# Spresense_PLC__Rev1-02.net
KiCad netlist of a schematic drawn in EAGLE
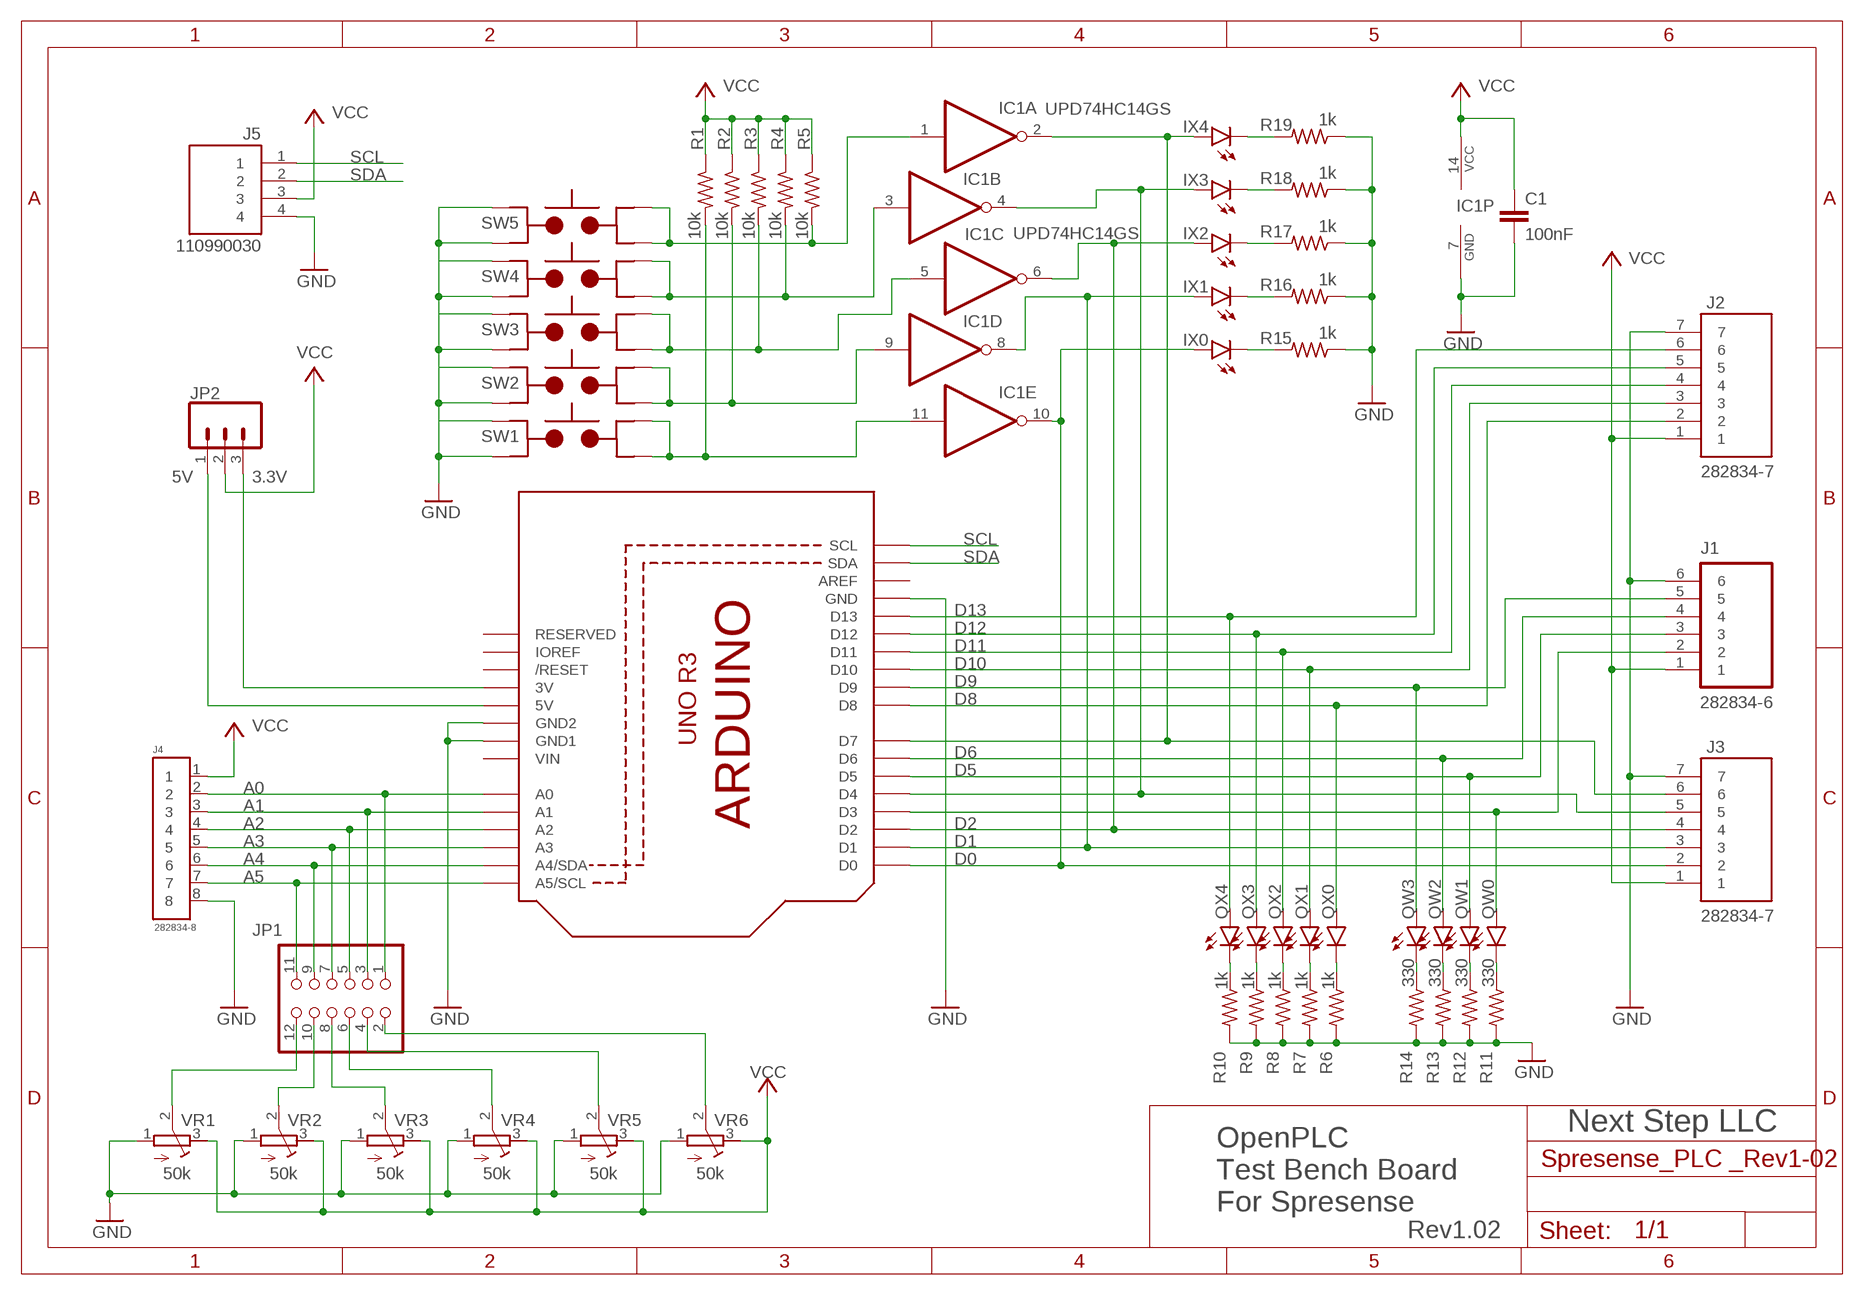
[diagram p0: schematic, sheet 1]

(export (version "E")
  (design (tool "Eeschema 10.0.6"))
  (components
    (comp (ref "C1")
      (value "100nF")
      (footprint "eagle-import:C0603")
      (libsource (lib "eagle-import") (part "C-EUC0603"))
    )
    (comp (ref "IC1")
      (value "UPD74HC14GS")
      (footprint "eagle-import:SO14")
      (libsource (lib "eagle-import") (part "7404DALS"))
    )
    (comp (ref "IX0")
      (value "LEDCHIP-LED0603")
      (footprint "eagle-import:CHIP-LED0603")
      (libsource (lib "eagle-import") (part "LEDCHIP-LED0603"))
    )
    (comp (ref "IX1")
      (value "LEDCHIP-LED0603")
      (footprint "eagle-import:CHIP-LED0603")
      (libsource (lib "eagle-import") (part "LEDCHIP-LED0603"))
    )
    (comp (ref "IX2")
      (value "LEDCHIP-LED0603")
      (footprint "eagle-import:CHIP-LED0603")
      (libsource (lib "eagle-import") (part "LEDCHIP-LED0603"))
    )
    (comp (ref "IX3")
      (value "LEDCHIP-LED0603")
      (footprint "eagle-import:CHIP-LED0603")
      (libsource (lib "eagle-import") (part "LEDCHIP-LED0603"))
    )
    (comp (ref "IX4")
      (value "LEDCHIP-LED0603")
      (footprint "eagle-import:CHIP-LED0603")
      (libsource (lib "eagle-import") (part "LEDCHIP-LED0603"))
    )
    (comp (ref "J1")
      (value "282834-6")
      (footprint "eagle-import:TE_282834-6")
      (fields (field (name "MF") "TE Connectivity"))
      (libsource (lib "eagle-import") (part "282834-6"))
    )
    (comp (ref "J2")
      (value "282834-7")
      (footprint "eagle-import:TE_282834-7")
      (fields (field (name "MF") "TE Connectivity"))
      (libsource (lib "eagle-import") (part "282834-7"))
    )
    (comp (ref "J3")
      (value "282834-7")
      (footprint "eagle-import:TE_282834-7")
      (fields (field (name "MF") "TE Connectivity"))
      (libsource (lib "eagle-import") (part "282834-7"))
    )
    (comp (ref "J4")
      (value "282834-8")
      (footprint "eagle-import:HDRV8W85P254_8X1_2078X650X1000")
      (fields (field (name "MF") "TE Connectivity"))
      (libsource (lib "eagle-import") (part "282834-8"))
    )
    (comp (ref "J5")
      (value "110990030")
      (footprint "eagle-import:SEEED_110990030")
      (fields (field (name "MF") "Seeed Technology Co., Ltd"))
      (libsource (lib "eagle-import") (part "110990030"))
    )
    (comp (ref "JP1")
      (value "PINHD-2X6")
      (footprint "eagle-import:2X06")
      (libsource (lib "eagle-import") (part "PINHD-2X6"))
    )
    (comp (ref "JP2")
      (value "455-1750-1-ND")
      (footprint "eagle-import:1X03")
      (libsource (lib "eagle-import") (part "CONN_03"))
    )
    (comp (ref "QW0")
      (value "LEDCHIP-LED0603")
      (footprint "eagle-import:CHIP-LED0603")
      (libsource (lib "eagle-import") (part "LEDCHIP-LED0603"))
    )
    (comp (ref "QW1")
      (value "LEDCHIP-LED0603")
      (footprint "eagle-import:CHIP-LED0603")
      (libsource (lib "eagle-import") (part "LEDCHIP-LED0603"))
    )
    (comp (ref "QW2")
      (value "LEDCHIP-LED0603")
      (footprint "eagle-import:CHIP-LED0603")
      (libsource (lib "eagle-import") (part "LEDCHIP-LED0603"))
    )
    (comp (ref "QW3")
      (value "LEDCHIP-LED0603")
      (footprint "eagle-import:CHIP-LED0603")
      (libsource (lib "eagle-import") (part "LEDCHIP-LED0603"))
    )
    (comp (ref "QX0")
      (value "LEDCHIP-LED0603")
      (footprint "eagle-import:CHIP-LED0603")
      (libsource (lib "eagle-import") (part "LEDCHIP-LED0603"))
    )
    (comp (ref "QX1")
      (value "LEDCHIP-LED0603")
      (footprint "eagle-import:CHIP-LED0603")
      (libsource (lib "eagle-import") (part "LEDCHIP-LED0603"))
    )
    (comp (ref "QX2")
      (value "LEDCHIP-LED0603")
      (footprint "eagle-import:CHIP-LED0603")
      (libsource (lib "eagle-import") (part "LEDCHIP-LED0603"))
    )
    (comp (ref "QX3")
      (value "LEDCHIP-LED0603")
      (footprint "eagle-import:CHIP-LED0603")
      (libsource (lib "eagle-import") (part "LEDCHIP-LED0603"))
    )
    (comp (ref "QX4")
      (value "LEDCHIP-LED0603")
      (footprint "eagle-import:CHIP-LED0603")
      (libsource (lib "eagle-import") (part "LEDCHIP-LED0603"))
    )
    (comp (ref "R1")
      (value "10k")
      (footprint "eagle-import:R0603")
      (libsource (lib "eagle-import") (part "R-US_R0603"))
    )
    (comp (ref "R2")
      (value "10k")
      (footprint "eagle-import:R0603")
      (libsource (lib "eagle-import") (part "R-US_R0603"))
    )
    (comp (ref "R3")
      (value "10k")
      (footprint "eagle-import:R0603")
      (libsource (lib "eagle-import") (part "R-US_R0603"))
    )
    (comp (ref "R4")
      (value "10k")
      (footprint "eagle-import:R0603")
      (libsource (lib "eagle-import") (part "R-US_R0603"))
    )
    (comp (ref "R5")
      (value "10k")
      (footprint "eagle-import:R0603")
      (libsource (lib "eagle-import") (part "R-US_R0603"))
    )
    (comp (ref "R6")
      (value "1k")
      (footprint "eagle-import:R0603")
      (libsource (lib "eagle-import") (part "R-US_R0603"))
    )
    (comp (ref "R7")
      (value "1k")
      (footprint "eagle-import:R0603")
      (libsource (lib "eagle-import") (part "R-US_R0603"))
    )
    (comp (ref "R8")
      (value "1k")
      (footprint "eagle-import:R0603")
      (libsource (lib "eagle-import") (part "R-US_R0603"))
    )
    (comp (ref "R9")
      (value "1k")
      (footprint "eagle-import:R0603")
      (libsource (lib "eagle-import") (part "R-US_R0603"))
    )
    (comp (ref "R10")
      (value "1k")
      (footprint "eagle-import:R0603")
      (libsource (lib "eagle-import") (part "R-US_R0603"))
    )
    (comp (ref "R11")
      (value "330")
      (footprint "eagle-import:R0603")
      (libsource (lib "eagle-import") (part "R-US_R0603"))
    )
    (comp (ref "R12")
      (value "330")
      (footprint "eagle-import:R0603")
      (libsource (lib "eagle-import") (part "R-US_R0603"))
    )
    (comp (ref "R13")
      (value "330")
      (footprint "eagle-import:R0603")
      (libsource (lib "eagle-import") (part "R-US_R0603"))
    )
    (comp (ref "R14")
      (value "330")
      (footprint "eagle-import:R0603")
      (libsource (lib "eagle-import") (part "R-US_R0603"))
    )
    (comp (ref "R15")
      (value "1k")
      (footprint "eagle-import:R0603")
      (libsource (lib "eagle-import") (part "R-US_R0603"))
    )
    (comp (ref "R16")
      (value "1k")
      (footprint "eagle-import:R0603")
      (libsource (lib "eagle-import") (part "R-US_R0603"))
    )
    (comp (ref "R17")
      (value "1k")
      (footprint "eagle-import:R0603")
      (libsource (lib "eagle-import") (part "R-US_R0603"))
    )
    (comp (ref "R18")
      (value "1k")
      (footprint "eagle-import:R0603")
      (libsource (lib "eagle-import") (part "R-US_R0603"))
    )
    (comp (ref "R19")
      (value "1k")
      (footprint "eagle-import:R0603")
      (libsource (lib "eagle-import") (part "R-US_R0603"))
    )
    (comp (ref "SW1")
      (value "TL3342F160QG/TR")
      (footprint "eagle-import:SW_TL3342F160QG_TR")
      (fields (field (name "MF") "E-Switch"))
      (libsource (lib "eagle-import") (part "TL3342F160QG/TR"))
    )
    (comp (ref "SW2")
      (value "TL3342F160QG/TR")
      (footprint "eagle-import:SW_TL3342F160QG_TR")
      (fields (field (name "MF") "E-Switch"))
      (libsource (lib "eagle-import") (part "TL3342F160QG/TR"))
    )
    (comp (ref "SW3")
      (value "TL3342F160QG/TR")
      (footprint "eagle-import:SW_TL3342F160QG_TR")
      (fields (field (name "MF") "E-Switch"))
      (libsource (lib "eagle-import") (part "TL3342F160QG/TR"))
    )
    (comp (ref "SW4")
      (value "TL3342F160QG/TR")
      (footprint "eagle-import:SW_TL3342F160QG_TR")
      (fields (field (name "MF") "E-Switch"))
      (libsource (lib "eagle-import") (part "TL3342F160QG/TR"))
    )
    (comp (ref "SW5")
      (value "TL3342F160QG/TR")
      (footprint "eagle-import:SW_TL3342F160QG_TR")
      (fields (field (name "MF") "E-Switch"))
      (libsource (lib "eagle-import") (part "TL3342F160QG/TR"))
    )
    (comp (ref "U1")
      (value "ARDUINOR3-DIMENSION")
      (footprint "eagle-import:ARDUINOR3")
      (libsource (lib "eagle-import") (part "ARDUINOR3-DIMENSION"))
    )
    (comp (ref "VR1")
      (value "50k")
      (footprint "eagle-import:RTRIM3339P")
      (libsource (lib "eagle-import") (part "R-TRIMM3339P"))
    )
    (comp (ref "VR2")
      (value "50k")
      (footprint "eagle-import:RTRIM3339P")
      (libsource (lib "eagle-import") (part "R-TRIMM3339P"))
    )
    (comp (ref "VR3")
      (value "50k")
      (footprint "eagle-import:RTRIM3339P")
      (libsource (lib "eagle-import") (part "R-TRIMM3339P"))
    )
    (comp (ref "VR4")
      (value "50k")
      (footprint "eagle-import:RTRIM3339P")
      (libsource (lib "eagle-import") (part "R-TRIMM3339P"))
    )
    (comp (ref "VR5")
      (value "50k")
      (footprint "eagle-import:RTRIM3339P")
      (libsource (lib "eagle-import") (part "R-TRIMM3339P"))
    )
    (comp (ref "VR6")
      (value "50k")
      (footprint "eagle-import:RTRIM3339P")
      (libsource (lib "eagle-import") (part "R-TRIMM3339P"))
    )
  )
  (nets
    (net (code "1") (name "/A0") (class "Default")
      (node (ref "J4") (pin "2") (pinfunction "2_2") (pintype "passive"))
      (node (ref "JP1") (pin "1") (pinfunction "1_1") (pintype "passive"))
      (node (ref "U1") (pin "A0") (pinfunction "A0_A0") (pintype "bidirectional"))
    )
    (net (code "2") (name "/A1") (class "Default")
      (node (ref "J4") (pin "3") (pinfunction "3_3") (pintype "passive"))
      (node (ref "JP1") (pin "3") (pinfunction "3_3") (pintype "passive"))
      (node (ref "U1") (pin "A1") (pinfunction "A1_A1") (pintype "bidirectional"))
    )
    (net (code "3") (name "/A2") (class "Default")
      (node (ref "J4") (pin "4") (pinfunction "4_4") (pintype "passive"))
      (node (ref "JP1") (pin "5") (pinfunction "5_5") (pintype "passive"))
      (node (ref "U1") (pin "A2") (pinfunction "A2_A2") (pintype "bidirectional"))
    )
    (net (code "4") (name "/A3") (class "Default")
      (node (ref "J4") (pin "5") (pinfunction "5_5") (pintype "passive"))
      (node (ref "JP1") (pin "7") (pinfunction "7_7") (pintype "passive"))
      (node (ref "U1") (pin "A3") (pinfunction "A3_A3") (pintype "bidirectional"))
    )
    (net (code "5") (name "/A4") (class "Default")
      (node (ref "J4") (pin "6") (pinfunction "6_6") (pintype "passive"))
      (node (ref "JP1") (pin "9") (pinfunction "9_9") (pintype "passive"))
      (node (ref "U1") (pin "A4") (pinfunction "A4/SDA_A4") (pintype "bidirectional"))
    )
    (net (code "6") (name "/A5") (class "Default")
      (node (ref "J4") (pin "7") (pinfunction "7_7") (pintype "passive"))
      (node (ref "JP1") (pin "11") (pinfunction "11_11") (pintype "passive"))
      (node (ref "U1") (pin "A5") (pinfunction "A5/SCL_A5") (pintype "bidirectional"))
    )
    (net (code "7") (name "/D0") (class "Default")
      (node (ref "IC1") (pin "10") (pinfunction "O_10") (pintype "output"))
      (node (ref "IX0") (pin "A") (pinfunction "A_A") (pintype "passive"))
      (node (ref "J3") (pin "2") (pinfunction "2_2") (pintype "passive"))
      (node (ref "U1") (pin "D0") (pinfunction "D0_D0") (pintype "bidirectional"))
    )
    (net (code "8") (name "/D1") (class "Default")
      (node (ref "IC1") (pin "8") (pinfunction "O_8") (pintype "output"))
      (node (ref "IX1") (pin "A") (pinfunction "A_A") (pintype "passive"))
      (node (ref "J3") (pin "3") (pinfunction "3_3") (pintype "passive"))
      (node (ref "U1") (pin "D1") (pinfunction "D1_D1") (pintype "bidirectional"))
    )
    (net (code "9") (name "/D2") (class "Default")
      (node (ref "IC1") (pin "6") (pinfunction "O_6") (pintype "output"))
      (node (ref "IX2") (pin "A") (pinfunction "A_A") (pintype "passive"))
      (node (ref "J3") (pin "4") (pinfunction "4_4") (pintype "passive"))
      (node (ref "U1") (pin "D2") (pinfunction "D2_D2") (pintype "bidirectional"))
    )
    (net (code "10") (name "/D5") (class "Default")
      (node (ref "IC1") (pin "4") (pinfunction "O_4") (pintype "output"))
      (node (ref "IX3") (pin "A") (pinfunction "A_A") (pintype "passive"))
      (node (ref "J3") (pin "5") (pinfunction "5_5") (pintype "passive"))
      (node (ref "U1") (pin "D4") (pinfunction "D4_D4") (pintype "bidirectional"))
    )
    (net (code "11") (name "/D6") (class "Default")
      (node (ref "IC1") (pin "2") (pinfunction "O_2") (pintype "output"))
      (node (ref "IX4") (pin "A") (pinfunction "A_A") (pintype "passive"))
      (node (ref "J3") (pin "6") (pinfunction "6_6") (pintype "passive"))
      (node (ref "U1") (pin "D7") (pinfunction "D7_D7") (pintype "bidirectional"))
    )
    (net (code "12") (name "/D8") (class "Default")
      (node (ref "J2") (pin "2") (pinfunction "2_2") (pintype "passive"))
      (node (ref "QX0") (pin "A") (pinfunction "A_A") (pintype "passive"))
      (node (ref "U1") (pin "D8") (pinfunction "D8_D8") (pintype "bidirectional"))
    )
    (net (code "13") (name "/D9") (class "Default")
      (node (ref "J1") (pin "5") (pinfunction "5_5") (pintype "passive"))
      (node (ref "QW3") (pin "A") (pinfunction "A_A") (pintype "passive"))
      (node (ref "U1") (pin "D9") (pinfunction "D9_D9") (pintype "bidirectional"))
    )
    (net (code "14") (name "/D10") (class "Default")
      (node (ref "J2") (pin "3") (pinfunction "3_3") (pintype "passive"))
      (node (ref "QX1") (pin "A") (pinfunction "A_A") (pintype "passive"))
      (node (ref "U1") (pin "D10") (pinfunction "D10_D10") (pintype "bidirectional"))
    )
    (net (code "15") (name "/D11") (class "Default")
      (node (ref "J2") (pin "4") (pinfunction "4_4") (pintype "passive"))
      (node (ref "QX2") (pin "A") (pinfunction "A_A") (pintype "passive"))
      (node (ref "U1") (pin "D11") (pinfunction "D11_D11") (pintype "bidirectional"))
    )
    (net (code "16") (name "/D12") (class "Default")
      (node (ref "J2") (pin "5") (pinfunction "5_5") (pintype "passive"))
      (node (ref "QX3") (pin "A") (pinfunction "A_A") (pintype "passive"))
      (node (ref "U1") (pin "D12") (pinfunction "D12_D12") (pintype "bidirectional"))
    )
    (net (code "17") (name "/D13") (class "Default")
      (node (ref "J2") (pin "6") (pinfunction "6_6") (pintype "passive"))
      (node (ref "QX4") (pin "A") (pinfunction "A_A") (pintype "passive"))
      (node (ref "U1") (pin "D13") (pinfunction "D13_D13") (pintype "bidirectional"))
    )
    (net (code "18") (name "/SCL") (class "Default")
      (node (ref "J5") (pin "1") (pinfunction "1_1") (pintype "passive"))
      (node (ref "U1") (pin "SCL") (pinfunction "SCL_SCL") (pintype "bidirectional"))
    )
    (net (code "19") (name "/SDA") (class "Default")
      (node (ref "J5") (pin "2") (pinfunction "2_2") (pintype "passive"))
      (node (ref "U1") (pin "SDA") (pinfunction "SDA_SDA") (pintype "bidirectional"))
    )
    (net (code "20") (name "/VIN") (class "Default")
      (node (ref "U1") (pin "VIN") (pinfunction "VIN_VIN") (pintype "power_in"))
    )
    (net (code "21") (name "GND") (class "Default")
      (node (ref "C1") (pin "2") (pinfunction "2_2") (pintype "passive"))
      (node (ref "IC1") (pin "7") (pinfunction "GND_7") (pintype "power_in"))
      (node (ref "J1") (pin "6") (pinfunction "6_6") (pintype "passive"))
      (node (ref "J2") (pin "7") (pinfunction "7_7") (pintype "passive"))
      (node (ref "J3") (pin "7") (pinfunction "7_7") (pintype "passive"))
      (node (ref "J4") (pin "8") (pinfunction "8_8") (pintype "passive"))
      (node (ref "J5") (pin "4") (pinfunction "4_4") (pintype "passive"))
      (node (ref "R10") (pin "2") (pinfunction "2_2") (pintype "passive"))
      (node (ref "R11") (pin "2") (pinfunction "2_2") (pintype "passive"))
      (node (ref "R12") (pin "2") (pinfunction "2_2") (pintype "passive"))
      (node (ref "R13") (pin "2") (pinfunction "2_2") (pintype "passive"))
      (node (ref "R14") (pin "2") (pinfunction "2_2") (pintype "passive"))
      (node (ref "R15") (pin "1") (pinfunction "1_1") (pintype "passive"))
      (node (ref "R16") (pin "1") (pinfunction "1_1") (pintype "passive"))
      (node (ref "R17") (pin "1") (pinfunction "1_1") (pintype "passive"))
      (node (ref "R18") (pin "1") (pinfunction "1_1") (pintype "passive"))
      (node (ref "R19") (pin "1") (pinfunction "1_1") (pintype "passive"))
      (node (ref "R6") (pin "2") (pinfunction "2_2") (pintype "passive"))
      (node (ref "R7") (pin "2") (pinfunction "2_2") (pintype "passive"))
      (node (ref "R8") (pin "2") (pinfunction "2_2") (pintype "passive"))
      (node (ref "R9") (pin "2") (pinfunction "2_2") (pintype "passive"))
      (node (ref "SW1") (pin "3") (pinfunction "3_3") (pintype "passive"))
      (node (ref "SW1") (pin "4") (pinfunction "4_4") (pintype "passive"))
      (node (ref "SW2") (pin "3") (pinfunction "3_3") (pintype "passive"))
      (node (ref "SW2") (pin "4") (pinfunction "4_4") (pintype "passive"))
      (node (ref "SW3") (pin "3") (pinfunction "3_3") (pintype "passive"))
      (node (ref "SW3") (pin "4") (pinfunction "4_4") (pintype "passive"))
      (node (ref "SW4") (pin "3") (pinfunction "3_3") (pintype "passive"))
      (node (ref "SW4") (pin "4") (pinfunction "4_4") (pintype "passive"))
      (node (ref "SW5") (pin "3") (pinfunction "3_3") (pintype "passive"))
      (node (ref "SW5") (pin "4") (pinfunction "4_4") (pintype "passive"))
      (node (ref "U1") (pin "GND") (pinfunction "GND_GND") (pintype "power_in"))
      (node (ref "U1") (pin "GND1") (pinfunction "GND1_GND1") (pintype "power_in"))
      (node (ref "U1") (pin "GND2") (pinfunction "GND2_GND2") (pintype "power_in"))
      (node (ref "VR1") (pin "1") (pinfunction "A_1") (pintype "passive"))
      (node (ref "VR2") (pin "1") (pinfunction "A_1") (pintype "passive"))
      (node (ref "VR3") (pin "1") (pinfunction "A_1") (pintype "passive"))
      (node (ref "VR4") (pin "1") (pinfunction "A_1") (pintype "passive"))
      (node (ref "VR5") (pin "1") (pinfunction "A_1") (pintype "passive"))
      (node (ref "VR6") (pin "1") (pinfunction "A_1") (pintype "passive"))
    )
    (net (code "22") (name "Net-(IC1A-I)") (class "Default")
      (node (ref "IC1") (pin "1") (pinfunction "I_1") (pintype "input"))
      (node (ref "R5") (pin "2") (pinfunction "2_2") (pintype "passive"))
      (node (ref "SW5") (pin "1") (pinfunction "1_1") (pintype "passive"))
      (node (ref "SW5") (pin "2") (pinfunction "2_2") (pintype "passive"))
    )
    (net (code "23") (name "Net-(IC1B-I)") (class "Default")
      (node (ref "IC1") (pin "3") (pinfunction "I_3") (pintype "input"))
      (node (ref "R4") (pin "2") (pinfunction "2_2") (pintype "passive"))
      (node (ref "SW4") (pin "1") (pinfunction "1_1") (pintype "passive"))
      (node (ref "SW4") (pin "2") (pinfunction "2_2") (pintype "passive"))
    )
    (net (code "24") (name "Net-(IC1C-I)") (class "Default")
      (node (ref "IC1") (pin "5") (pinfunction "I_5") (pintype "input"))
      (node (ref "R3") (pin "2") (pinfunction "2_2") (pintype "passive"))
      (node (ref "SW3") (pin "1") (pinfunction "1_1") (pintype "passive"))
      (node (ref "SW3") (pin "2") (pinfunction "2_2") (pintype "passive"))
    )
    (net (code "25") (name "Net-(IC1D-I)") (class "Default")
      (node (ref "IC1") (pin "9") (pinfunction "I_9") (pintype "input"))
      (node (ref "R2") (pin "2") (pinfunction "2_2") (pintype "passive"))
      (node (ref "SW2") (pin "1") (pinfunction "1_1") (pintype "passive"))
      (node (ref "SW2") (pin "2") (pinfunction "2_2") (pintype "passive"))
    )
    (net (code "26") (name "Net-(IC1E-I)") (class "Default")
      (node (ref "IC1") (pin "11") (pinfunction "I_11") (pintype "input"))
      (node (ref "R1") (pin "2") (pinfunction "2_2") (pintype "passive"))
      (node (ref "SW1") (pin "1") (pinfunction "1_1") (pintype "passive"))
      (node (ref "SW1") (pin "2") (pinfunction "2_2") (pintype "passive"))
    )
    (net (code "27") (name "Net-(IX0-PadC)") (class "Default")
      (node (ref "IX0") (pin "C") (pinfunction "C_C") (pintype "passive"))
      (node (ref "R15") (pin "2") (pinfunction "2_2") (pintype "passive"))
    )
    (net (code "28") (name "Net-(IX1-PadC)") (class "Default")
      (node (ref "IX1") (pin "C") (pinfunction "C_C") (pintype "passive"))
      (node (ref "R16") (pin "2") (pinfunction "2_2") (pintype "passive"))
    )
    (net (code "29") (name "Net-(IX2-PadC)") (class "Default")
      (node (ref "IX2") (pin "C") (pinfunction "C_C") (pintype "passive"))
      (node (ref "R17") (pin "2") (pinfunction "2_2") (pintype "passive"))
    )
    (net (code "30") (name "Net-(IX3-PadC)") (class "Default")
      (node (ref "IX3") (pin "C") (pinfunction "C_C") (pintype "passive"))
      (node (ref "R18") (pin "2") (pinfunction "2_2") (pintype "passive"))
    )
    (net (code "31") (name "Net-(IX4-PadC)") (class "Default")
      (node (ref "IX4") (pin "C") (pinfunction "C_C") (pintype "passive"))
      (node (ref "R19") (pin "2") (pinfunction "2_2") (pintype "passive"))
    )
    (net (code "32") (name "Net-(J1-Pad2)") (class "Default")
      (node (ref "J1") (pin "2") (pinfunction "2_2") (pintype "passive"))
      (node (ref "QW0") (pin "A") (pinfunction "A_A") (pintype "passive"))
      (node (ref "U1") (pin "D3") (pinfunction "D3_D3") (pintype "bidirectional"))
    )
    (net (code "33") (name "Net-(J1-Pad3)") (class "Default")
      (node (ref "J1") (pin "3") (pinfunction "3_3") (pintype "passive"))
      (node (ref "QW1") (pin "A") (pinfunction "A_A") (pintype "passive"))
      (node (ref "U1") (pin "D5") (pinfunction "D5_D5") (pintype "bidirectional"))
    )
    (net (code "34") (name "Net-(J1-Pad4)") (class "Default")
      (node (ref "J1") (pin "4") (pinfunction "4_4") (pintype "passive"))
      (node (ref "QW2") (pin "A") (pinfunction "A_A") (pintype "passive"))
      (node (ref "U1") (pin "D6") (pinfunction "D6_D6") (pintype "bidirectional"))
    )
    (net (code "35") (name "Net-(JP2-Pad1)") (class "Default")
      (node (ref "JP2") (pin "1") (pinfunction "1_1") (pintype "passive"))
      (node (ref "U1") (pin "5V") (pinfunction "5V_5V") (pintype "power_in"))
    )
    (net (code "36") (name "Net-(JP2-Pad3)") (class "Default")
      (node (ref "JP2") (pin "3") (pinfunction "3_3") (pintype "passive"))
      (node (ref "U1") (pin "3V") (pinfunction "3V_3V") (pintype "power_in"))
    )
    (net (code "37") (name "Net-(QW0-PadC)") (class "Default")
      (node (ref "QW0") (pin "C") (pinfunction "C_C") (pintype "passive"))
      (node (ref "R11") (pin "1") (pinfunction "1_1") (pintype "passive"))
    )
    (net (code "38") (name "Net-(QW1-PadC)") (class "Default")
      (node (ref "QW1") (pin "C") (pinfunction "C_C") (pintype "passive"))
      (node (ref "R12") (pin "1") (pinfunction "1_1") (pintype "passive"))
    )
    (net (code "39") (name "Net-(QW2-PadC)") (class "Default")
      (node (ref "QW2") (pin "C") (pinfunction "C_C") (pintype "passive"))
      (node (ref "R13") (pin "1") (pinfunction "1_1") (pintype "passive"))
    )
    (net (code "40") (name "Net-(QW3-PadC)") (class "Default")
      (node (ref "QW3") (pin "C") (pinfunction "C_C") (pintype "passive"))
      (node (ref "R14") (pin "1") (pinfunction "1_1") (pintype "passive"))
    )
    (net (code "41") (name "Net-(QX0-PadC)") (class "Default")
      (node (ref "QX0") (pin "C") (pinfunction "C_C") (pintype "passive"))
      (node (ref "R6") (pin "1") (pinfunction "1_1") (pintype "passive"))
    )
    (net (code "42") (name "Net-(QX1-PadC)") (class "Default")
      (node (ref "QX1") (pin "C") (pinfunction "C_C") (pintype "passive"))
      (node (ref "R7") (pin "1") (pinfunction "1_1") (pintype "passive"))
    )
    (net (code "43") (name "Net-(QX2-PadC)") (class "Default")
      (node (ref "QX2") (pin "C") (pinfunction "C_C") (pintype "passive"))
      (node (ref "R8") (pin "1") (pinfunction "1_1") (pintype "passive"))
    )
    (net (code "44") (name "Net-(QX3-PadC)") (class "Default")
      (node (ref "QX3") (pin "C") (pinfunction "C_C") (pintype "passive"))
      (node (ref "R9") (pin "1") (pinfunction "1_1") (pintype "passive"))
    )
    (net (code "45") (name "Net-(QX4-PadC)") (class "Default")
      (node (ref "QX4") (pin "C") (pinfunction "C_C") (pintype "passive"))
      (node (ref "R10") (pin "1") (pinfunction "1_1") (pintype "passive"))
    )
    (net (code "46") (name "Net-(VR1-S)") (class "Default")
      (node (ref "JP1") (pin "12") (pinfunction "12_12") (pintype "passive"))
      (node (ref "VR1") (pin "2") (pinfunction "S_2") (pintype "passive"))
    )
    (net (code "47") (name "Net-(VR2-S)") (class "Default")
      (node (ref "JP1") (pin "10") (pinfunction "10_10") (pintype "passive"))
      (node (ref "VR2") (pin "2") (pinfunction "S_2") (pintype "passive"))
    )
    (net (code "48") (name "Net-(VR3-S)") (class "Default")
      (node (ref "JP1") (pin "8") (pinfunction "8_8") (pintype "passive"))
      (node (ref "VR3") (pin "2") (pinfunction "S_2") (pintype "passive"))
    )
    (net (code "49") (name "Net-(VR4-S)") (class "Default")
      (node (ref "JP1") (pin "6") (pinfunction "6_6") (pintype "passive"))
      (node (ref "VR4") (pin "2") (pinfunction "S_2") (pintype "passive"))
    )
    (net (code "50") (name "Net-(VR5-S)") (class "Default")
      (node (ref "JP1") (pin "4") (pinfunction "4_4") (pintype "passive"))
      (node (ref "VR5") (pin "2") (pinfunction "S_2") (pintype "passive"))
    )
    (net (code "51") (name "Net-(VR6-S)") (class "Default")
      (node (ref "JP1") (pin "2") (pinfunction "2_2") (pintype "passive"))
      (node (ref "VR6") (pin "2") (pinfunction "S_2") (pintype "passive"))
    )
    (net (code "52") (name "VCC") (class "Default")
      (node (ref "C1") (pin "1") (pinfunction "1_1") (pintype "passive"))
      (node (ref "IC1") (pin "14") (pinfunction "VCC_14") (pintype "power_in"))
      (node (ref "J1") (pin "1") (pinfunction "1_1") (pintype "passive"))
      (node (ref "J2") (pin "1") (pinfunction "1_1") (pintype "passive"))
      (node (ref "J3") (pin "1") (pinfunction "1_1") (pintype "passive"))
      (node (ref "J4") (pin "1") (pinfunction "1_1") (pintype "passive"))
      (node (ref "J5") (pin "3") (pinfunction "3_3") (pintype "passive"))
      (node (ref "JP2") (pin "2") (pinfunction "2_2") (pintype "passive"))
      (node (ref "R1") (pin "1") (pinfunction "1_1") (pintype "passive"))
      (node (ref "R2") (pin "1") (pinfunction "1_1") (pintype "passive"))
      (node (ref "R3") (pin "1") (pinfunction "1_1") (pintype "passive"))
      (node (ref "R4") (pin "1") (pinfunction "1_1") (pintype "passive"))
      (node (ref "R5") (pin "1") (pinfunction "1_1") (pintype "passive"))
      (node (ref "VR1") (pin "3") (pinfunction "E_3") (pintype "passive"))
      (node (ref "VR2") (pin "3") (pinfunction "E_3") (pintype "passive"))
      (node (ref "VR3") (pin "3") (pinfunction "E_3") (pintype "passive"))
      (node (ref "VR4") (pin "3") (pinfunction "E_3") (pintype "passive"))
      (node (ref "VR5") (pin "3") (pinfunction "E_3") (pintype "passive"))
      (node (ref "VR6") (pin "3") (pinfunction "E_3") (pintype "passive"))
    )
    (net (code "53") (name "unconnected-(U1-PadAREF)") (class "Default")
      (node (ref "U1") (pin "AREF") (pinfunction "AREF_AREF") (pintype "bidirectional"))
    )
    (net (code "54") (name "unconnected-(U1-PadIOREF)") (class "Default")
      (node (ref "U1") (pin "IOREF") (pinfunction "IOREF_IOREF") (pintype "output"))
    )
    (net (code "55") (name "unconnected-(U1-PadRESERVED)") (class "Default")
      (node (ref "U1") (pin "RESERVED") (pinfunction "RESERVED_RESERVED") (pintype "no_connect"))
    )
    (net (code "56") (name "unconnected-(U1-{slash}RESET-PadRESET)") (class "Default")
      (node (ref "U1") (pin "RESET") (pinfunction "/RESET_RESET") (pintype "bidirectional"))
    )
  )
)
